# jmb575.net
KiCad netlist of a schematic drawn in Altium Designer
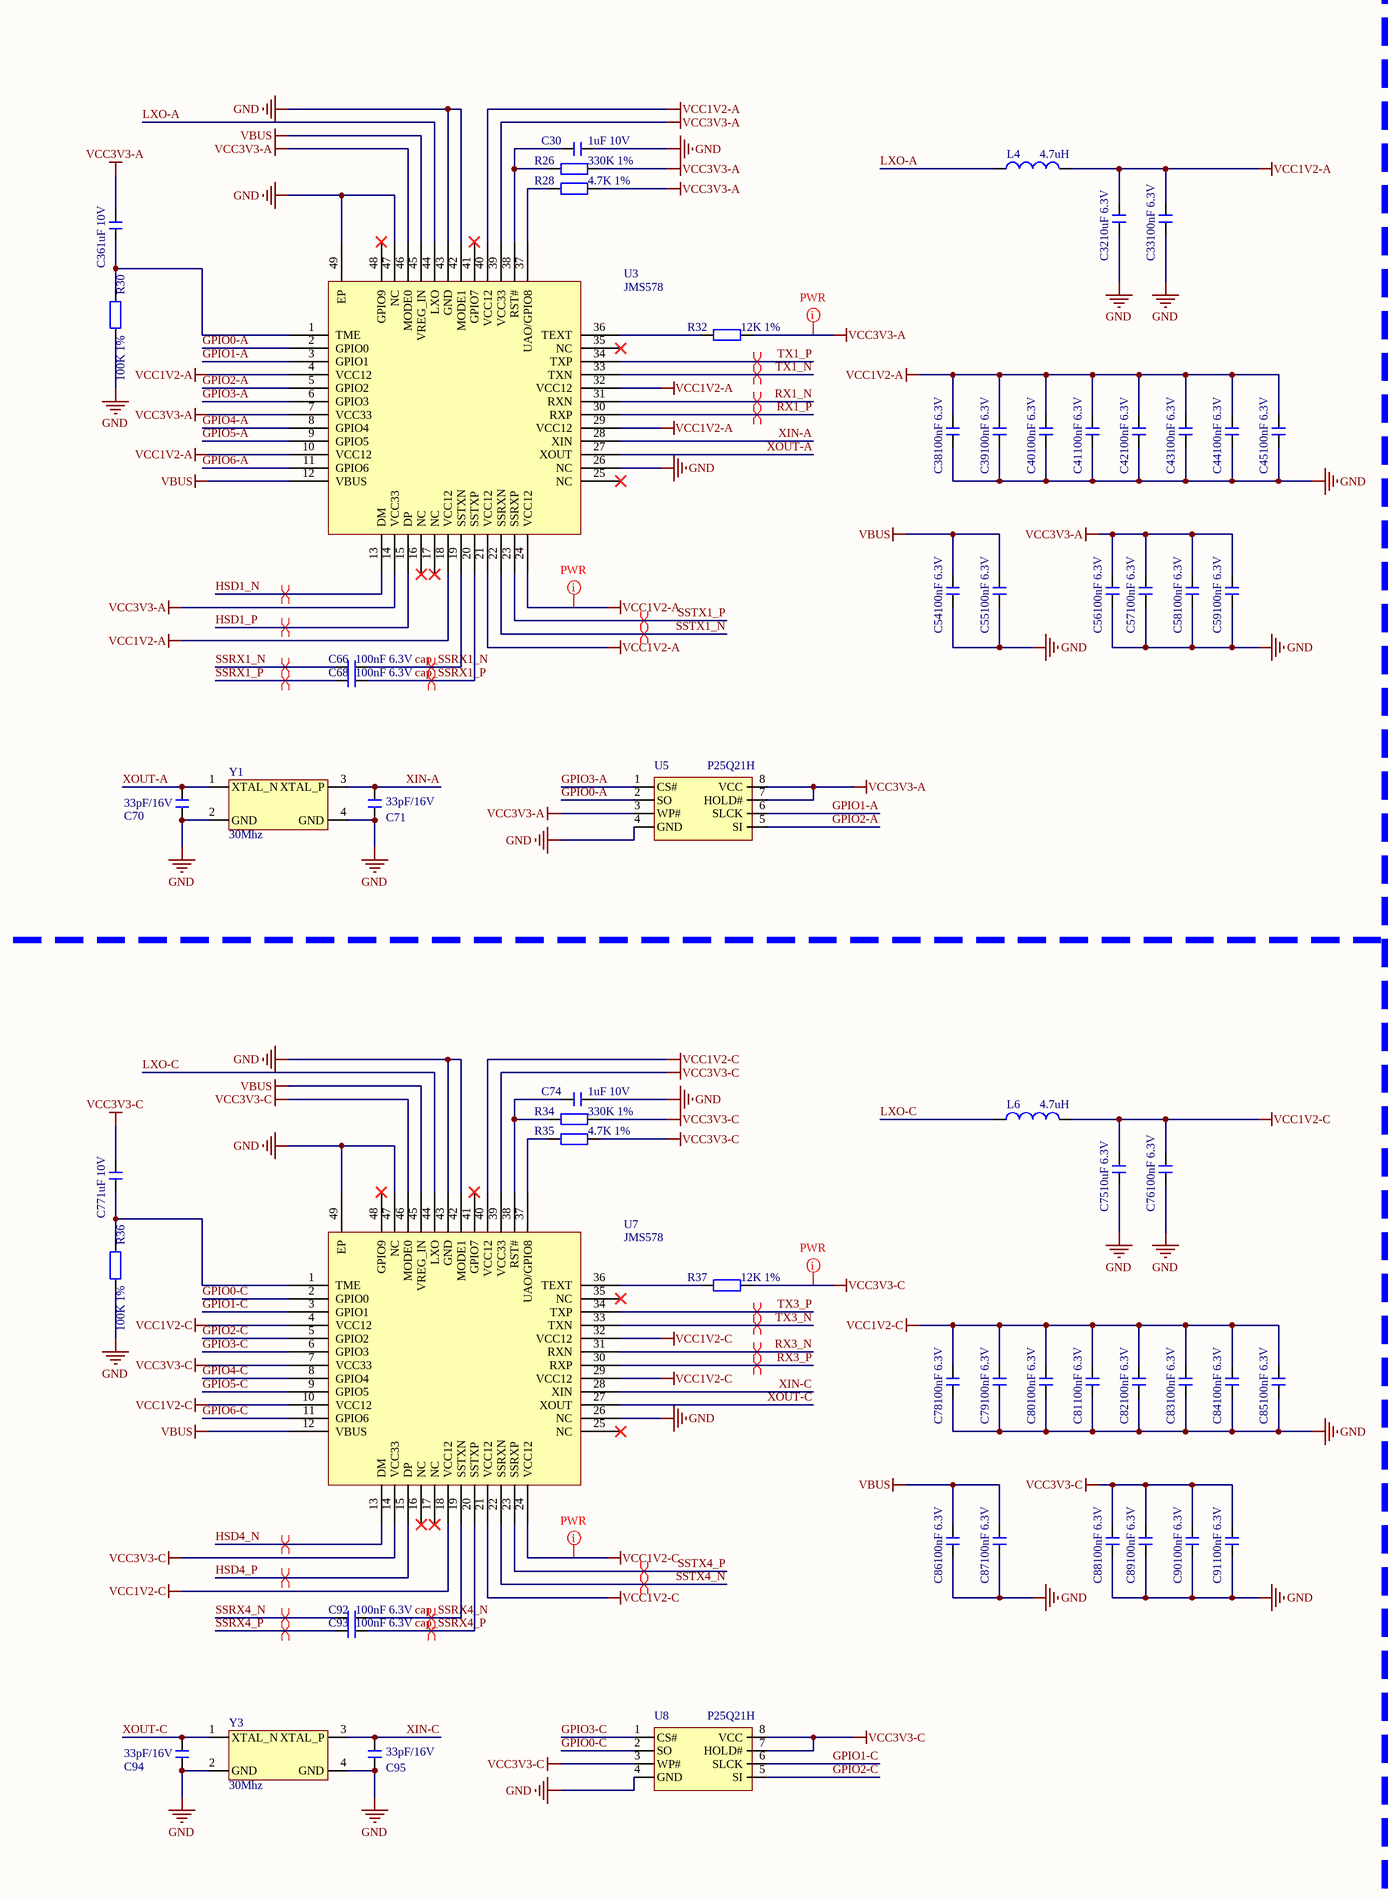
[diagram p0: jmb575.SchDoc, left]
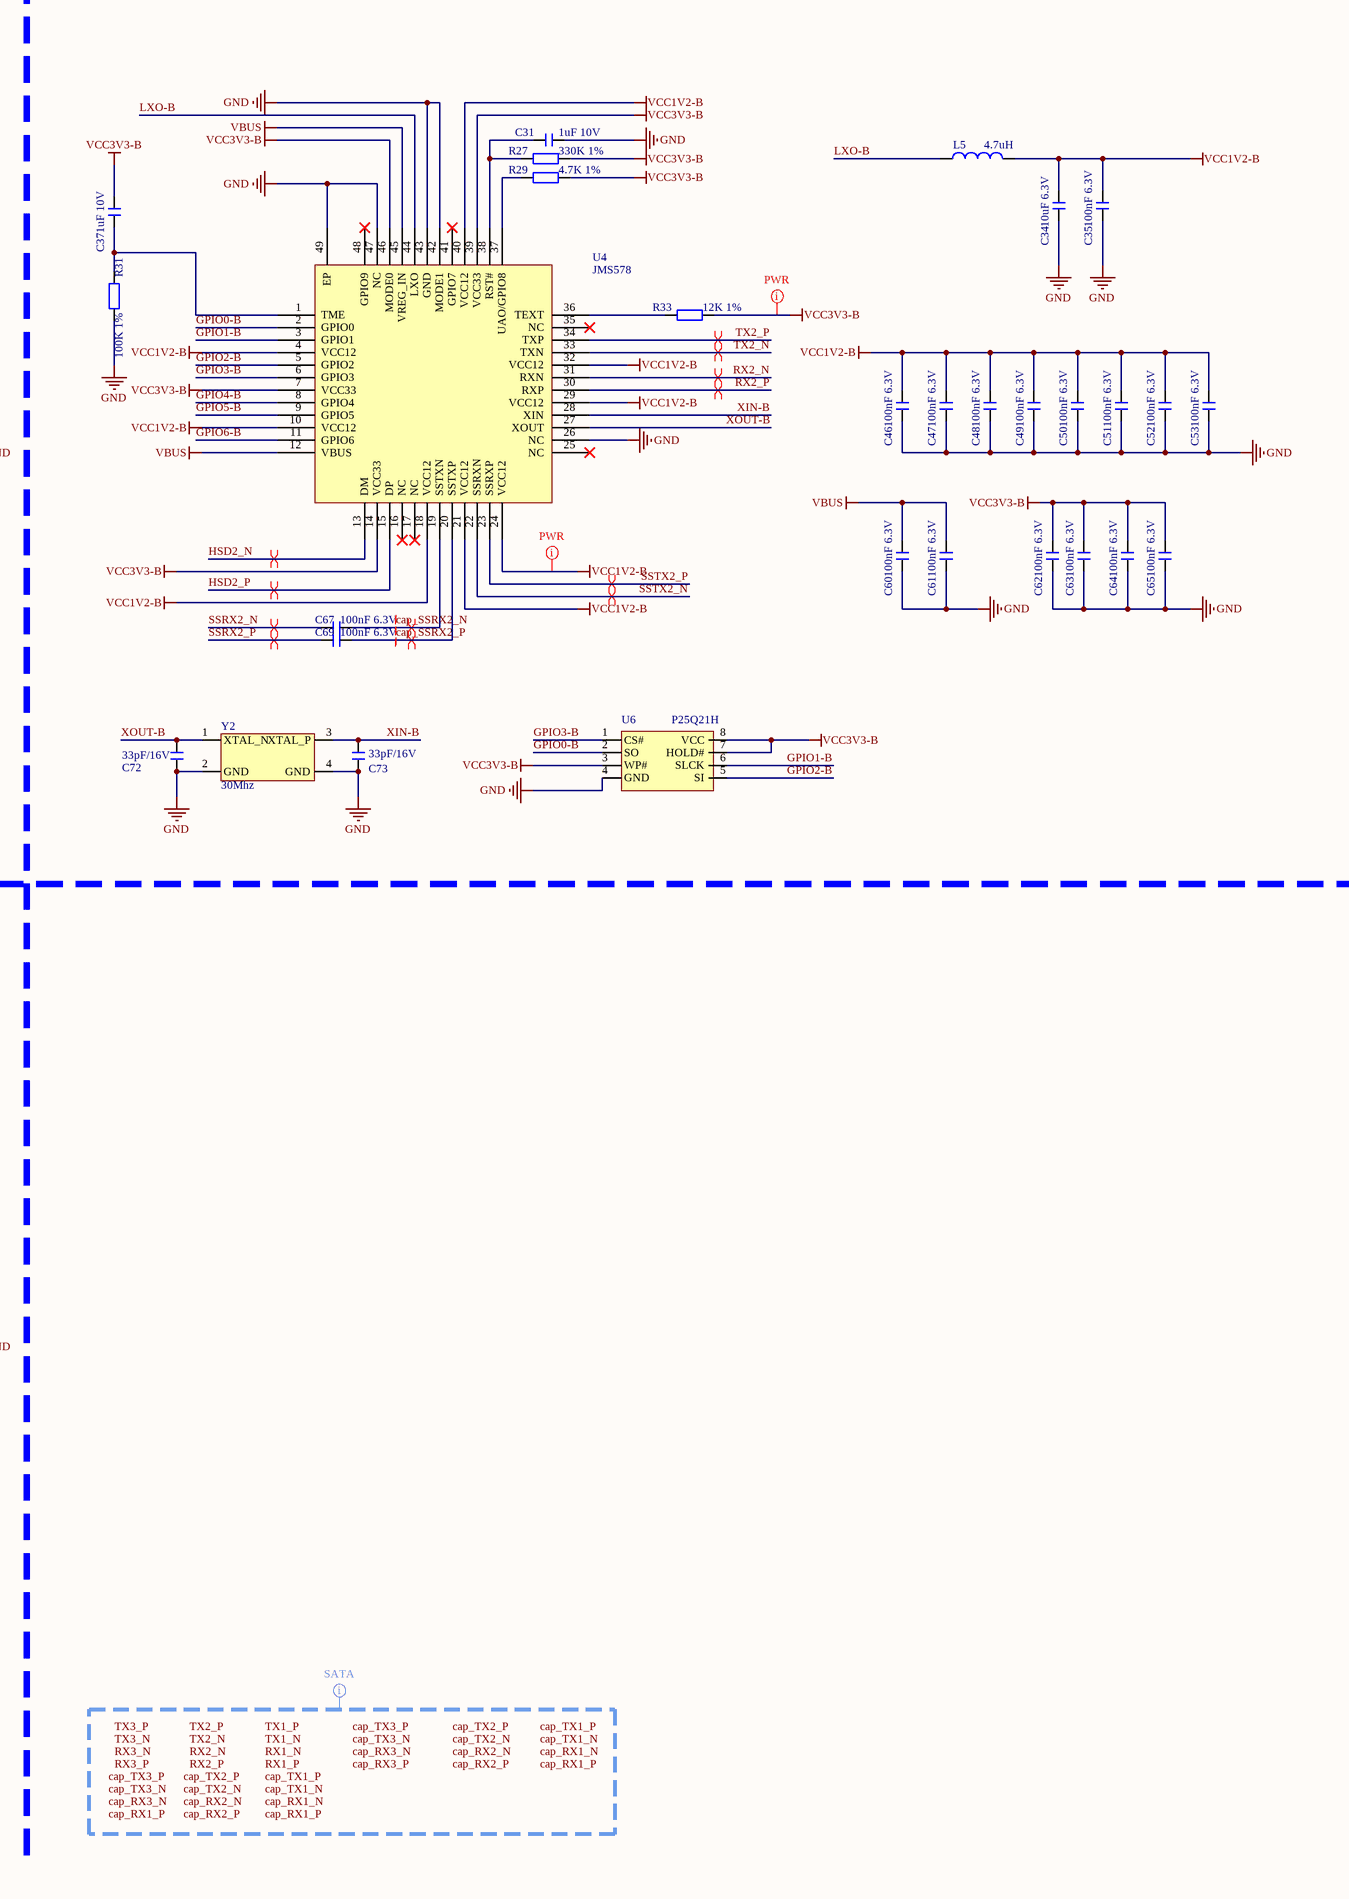
[diagram p1: jmb575.SchDoc, right]

(export (version "E")
  (design (tool "Eeschema 10.0.6"))
  (components
    (comp (ref "C30")
      (value "1uF 10V")
      (footprint "C0402_L")
      (description "无极性贴片电容")
      (fields (field (name "版权归属") "源创客"))
      (libsource (lib "Capacitor") (part "C"))
    )
    (comp (ref "C31")
      (value "1uF 10V")
      (footprint "C0402_L")
      (description "无极性贴片电容")
      (fields (field (name "版权归属") "源创客"))
      (libsource (lib "Capacitor") (part "C"))
    )
    (comp (ref "C32")
      (value "10uF 6.3V")
      (footprint "C0603_L")
      (description "无极性贴片电容")
      (fields (field (name "版权归属") "源创客"))
      (libsource (lib "Capacitor") (part "C"))
    )
    (comp (ref "C33")
      (value "100nF 6.3V")
      (footprint "C0402_L")
      (description "无极性贴片电容")
      (fields (field (name "版权归属") "源创客"))
      (libsource (lib "Capacitor") (part "C"))
    )
    (comp (ref "C34")
      (value "10uF 6.3V")
      (footprint "C0603_L")
      (description "无极性贴片电容")
      (fields (field (name "版权归属") "源创客"))
      (libsource (lib "Capacitor") (part "C"))
    )
    (comp (ref "C35")
      (value "100nF 6.3V")
      (footprint "C0402_L")
      (description "无极性贴片电容")
      (fields (field (name "版权归属") "源创客"))
      (libsource (lib "Capacitor") (part "C"))
    )
    (comp (ref "C36")
      (value "1uF 10V")
      (footprint "C0402_L")
      (description "无极性贴片电容")
      (fields (field (name "版权归属") "源创客"))
      (libsource (lib "Capacitor") (part "C"))
    )
    (comp (ref "C37")
      (value "1uF 10V")
      (footprint "C0402_L")
      (description "无极性贴片电容")
      (fields (field (name "版权归属") "源创客"))
      (libsource (lib "Capacitor") (part "C"))
    )
    (comp (ref "C38")
      (value "100nF 6.3V")
      (footprint "C0402_L")
      (description "无极性贴片电容")
      (fields (field (name "版权归属") "源创客"))
      (libsource (lib "Capacitor") (part "C"))
    )
    (comp (ref "C39")
      (value "100nF 6.3V")
      (footprint "C0402_L")
      (description "无极性贴片电容")
      (fields (field (name "版权归属") "源创客"))
      (libsource (lib "Capacitor") (part "C"))
    )
    (comp (ref "C40")
      (value "100nF 6.3V")
      (footprint "C0402_L")
      (description "无极性贴片电容")
      (fields (field (name "版权归属") "源创客"))
      (libsource (lib "Capacitor") (part "C"))
    )
    (comp (ref "C41")
      (value "100nF 6.3V")
      (footprint "C0402_L")
      (description "无极性贴片电容")
      (fields (field (name "版权归属") "源创客"))
      (libsource (lib "Capacitor") (part "C"))
    )
    (comp (ref "C42")
      (value "100nF 6.3V")
      (footprint "C0402_L")
      (description "无极性贴片电容")
      (fields (field (name "版权归属") "源创客"))
      (libsource (lib "Capacitor") (part "C"))
    )
    (comp (ref "C43")
      (value "100nF 6.3V")
      (footprint "C0402_L")
      (description "无极性贴片电容")
      (fields (field (name "版权归属") "源创客"))
      (libsource (lib "Capacitor") (part "C"))
    )
    (comp (ref "C44")
      (value "100nF 6.3V")
      (footprint "C0402_L")
      (description "无极性贴片电容")
      (fields (field (name "版权归属") "源创客"))
      (libsource (lib "Capacitor") (part "C"))
    )
    (comp (ref "C45")
      (value "100nF 6.3V")
      (footprint "C0402_L")
      (description "无极性贴片电容")
      (fields (field (name "版权归属") "源创客"))
      (libsource (lib "Capacitor") (part "C"))
    )
    (comp (ref "C46")
      (value "100nF 6.3V")
      (footprint "C0402_L")
      (description "无极性贴片电容")
      (fields (field (name "版权归属") "源创客"))
      (libsource (lib "Capacitor") (part "C"))
    )
    (comp (ref "C47")
      (value "100nF 6.3V")
      (footprint "C0402_L")
      (description "无极性贴片电容")
      (fields (field (name "版权归属") "源创客"))
      (libsource (lib "Capacitor") (part "C"))
    )
    (comp (ref "C48")
      (value "100nF 6.3V")
      (footprint "C0402_L")
      (description "无极性贴片电容")
      (fields (field (name "版权归属") "源创客"))
      (libsource (lib "Capacitor") (part "C"))
    )
    (comp (ref "C49")
      (value "100nF 6.3V")
      (footprint "C0402_L")
      (description "无极性贴片电容")
      (fields (field (name "版权归属") "源创客"))
      (libsource (lib "Capacitor") (part "C"))
    )
    (comp (ref "C50")
      (value "100nF 6.3V")
      (footprint "C0402_L")
      (description "无极性贴片电容")
      (fields (field (name "版权归属") "源创客"))
      (libsource (lib "Capacitor") (part "C"))
    )
    (comp (ref "C51")
      (value "100nF 6.3V")
      (footprint "C0402_L")
      (description "无极性贴片电容")
      (fields (field (name "版权归属") "源创客"))
      (libsource (lib "Capacitor") (part "C"))
    )
    (comp (ref "C52")
      (value "100nF 6.3V")
      (footprint "C0402_L")
      (description "无极性贴片电容")
      (fields (field (name "版权归属") "源创客"))
      (libsource (lib "Capacitor") (part "C"))
    )
    (comp (ref "C53")
      (value "100nF 6.3V")
      (footprint "C0402_L")
      (description "无极性贴片电容")
      (fields (field (name "版权归属") "源创客"))
      (libsource (lib "Capacitor") (part "C"))
    )
    (comp (ref "C54")
      (value "100nF 6.3V")
      (footprint "C0402_L")
      (description "无极性贴片电容")
      (fields (field (name "版权归属") "源创客"))
      (libsource (lib "Capacitor") (part "C"))
    )
    (comp (ref "C55")
      (value "100nF 6.3V")
      (footprint "C0402_L")
      (description "无极性贴片电容")
      (fields (field (name "版权归属") "源创客"))
      (libsource (lib "Capacitor") (part "C"))
    )
    (comp (ref "C56")
      (value "100nF 6.3V")
      (footprint "C0402_L")
      (description "无极性贴片电容")
      (fields (field (name "版权归属") "源创客"))
      (libsource (lib "Capacitor") (part "C"))
    )
    (comp (ref "C57")
      (value "100nF 6.3V")
      (footprint "C0402_L")
      (description "无极性贴片电容")
      (fields (field (name "版权归属") "源创客"))
      (libsource (lib "Capacitor") (part "C"))
    )
    (comp (ref "C58")
      (value "100nF 6.3V")
      (footprint "C0402_L")
      (description "无极性贴片电容")
      (fields (field (name "版权归属") "源创客"))
      (libsource (lib "Capacitor") (part "C"))
    )
    (comp (ref "C59")
      (value "100nF 6.3V")
      (footprint "C0402_L")
      (description "无极性贴片电容")
      (fields (field (name "版权归属") "源创客"))
      (libsource (lib "Capacitor") (part "C"))
    )
    (comp (ref "C60")
      (value "100nF 6.3V")
      (footprint "C0402_L")
      (description "无极性贴片电容")
      (fields (field (name "版权归属") "源创客"))
      (libsource (lib "Capacitor") (part "C"))
    )
    (comp (ref "C61")
      (value "100nF 6.3V")
      (footprint "C0402_L")
      (description "无极性贴片电容")
      (fields (field (name "版权归属") "源创客"))
      (libsource (lib "Capacitor") (part "C"))
    )
    (comp (ref "C62")
      (value "100nF 6.3V")
      (footprint "C0402_L")
      (description "无极性贴片电容")
      (fields (field (name "版权归属") "源创客"))
      (libsource (lib "Capacitor") (part "C"))
    )
    (comp (ref "C63")
      (value "100nF 6.3V")
      (footprint "C0402_L")
      (description "无极性贴片电容")
      (fields (field (name "版权归属") "源创客"))
      (libsource (lib "Capacitor") (part "C"))
    )
    (comp (ref "C64")
      (value "100nF 6.3V")
      (footprint "C0402_L")
      (description "无极性贴片电容")
      (fields (field (name "版权归属") "源创客"))
      (libsource (lib "Capacitor") (part "C"))
    )
    (comp (ref "C65")
      (value "100nF 6.3V")
      (footprint "C0402_L")
      (description "无极性贴片电容")
      (fields (field (name "版权归属") "源创客"))
      (libsource (lib "Capacitor") (part "C"))
    )
    (comp (ref "C66")
      (value "100nF 6.3V")
      (footprint "C0402_L")
      (description "无极性贴片电容")
      (fields (field (name "版权归属") "源创客"))
      (libsource (lib "Capacitor") (part "C"))
    )
    (comp (ref "C67")
      (value "100nF 6.3V")
      (footprint "C0402_L")
      (description "无极性贴片电容")
      (fields (field (name "版权归属") "源创客"))
      (libsource (lib "Capacitor") (part "C"))
    )
    (comp (ref "C68")
      (value "100nF 6.3V")
      (footprint "C0402_L")
      (description "无极性贴片电容")
      (fields (field (name "版权归属") "源创客"))
      (libsource (lib "Capacitor") (part "C"))
    )
    (comp (ref "C69")
      (value "100nF 6.3V")
      (footprint "C0402_L")
      (description "无极性贴片电容")
      (fields (field (name "版权归属") "源创客"))
      (libsource (lib "Capacitor") (part "C"))
    )
    (comp (ref "C70")
      (value "33pF/16V")
      (footprint "C0402_L")
      (description "无极性贴片电容")
      (fields (field (name "版权归属") "源创客"))
      (libsource (lib "Capacitor") (part "C"))
    )
    (comp (ref "C71")
      (value "33pF/16V")
      (footprint "C0402_L")
      (description "无极性贴片电容")
      (fields (field (name "版权归属") "源创客"))
      (libsource (lib "Capacitor") (part "C"))
    )
    (comp (ref "C72")
      (value "33pF/16V")
      (footprint "C0402_L")
      (description "无极性贴片电容")
      (fields (field (name "版权归属") "源创客"))
      (libsource (lib "Capacitor") (part "C"))
    )
    (comp (ref "C73")
      (value "33pF/16V")
      (footprint "C0402_L")
      (description "无极性贴片电容")
      (fields (field (name "版权归属") "源创客"))
      (libsource (lib "Capacitor") (part "C"))
    )
    (comp (ref "C74")
      (value "1uF 10V")
      (footprint "C0402_L")
      (description "无极性贴片电容")
      (fields (field (name "版权归属") "源创客"))
      (libsource (lib "Capacitor") (part "C"))
    )
    (comp (ref "C75")
      (value "10uF 6.3V")
      (footprint "C0603_L")
      (description "无极性贴片电容")
      (fields (field (name "版权归属") "源创客"))
      (libsource (lib "Capacitor") (part "C"))
    )
    (comp (ref "C76")
      (value "100nF 6.3V")
      (footprint "C0402_L")
      (description "无极性贴片电容")
      (fields (field (name "版权归属") "源创客"))
      (libsource (lib "Capacitor") (part "C"))
    )
    (comp (ref "C77")
      (value "1uF 10V")
      (footprint "C0402_L")
      (description "无极性贴片电容")
      (fields (field (name "版权归属") "源创客"))
      (libsource (lib "Capacitor") (part "C"))
    )
    (comp (ref "C78")
      (value "100nF 6.3V")
      (footprint "C0402_L")
      (description "无极性贴片电容")
      (fields (field (name "版权归属") "源创客"))
      (libsource (lib "Capacitor") (part "C"))
    )
    (comp (ref "C79")
      (value "100nF 6.3V")
      (footprint "C0402_L")
      (description "无极性贴片电容")
      (fields (field (name "版权归属") "源创客"))
      (libsource (lib "Capacitor") (part "C"))
    )
    (comp (ref "C80")
      (value "100nF 6.3V")
      (footprint "C0402_L")
      (description "无极性贴片电容")
      (fields (field (name "版权归属") "源创客"))
      (libsource (lib "Capacitor") (part "C"))
    )
    (comp (ref "C81")
      (value "100nF 6.3V")
      (footprint "C0402_L")
      (description "无极性贴片电容")
      (fields (field (name "版权归属") "源创客"))
      (libsource (lib "Capacitor") (part "C"))
    )
    (comp (ref "C82")
      (value "100nF 6.3V")
      (footprint "C0402_L")
      (description "无极性贴片电容")
      (fields (field (name "版权归属") "源创客"))
      (libsource (lib "Capacitor") (part "C"))
    )
    (comp (ref "C83")
      (value "100nF 6.3V")
      (footprint "C0402_L")
      (description "无极性贴片电容")
      (fields (field (name "版权归属") "源创客"))
      (libsource (lib "Capacitor") (part "C"))
    )
    (comp (ref "C84")
      (value "100nF 6.3V")
      (footprint "C0402_L")
      (description "无极性贴片电容")
      (fields (field (name "版权归属") "源创客"))
      (libsource (lib "Capacitor") (part "C"))
    )
    (comp (ref "C85")
      (value "100nF 6.3V")
      (footprint "C0402_L")
      (description "无极性贴片电容")
      (fields (field (name "版权归属") "源创客"))
      (libsource (lib "Capacitor") (part "C"))
    )
    (comp (ref "C86")
      (value "100nF 6.3V")
      (footprint "C0402_L")
      (description "无极性贴片电容")
      (fields (field (name "版权归属") "源创客"))
      (libsource (lib "Capacitor") (part "C"))
    )
    (comp (ref "C87")
      (value "100nF 6.3V")
      (footprint "C0402_L")
      (description "无极性贴片电容")
      (fields (field (name "版权归属") "源创客"))
      (libsource (lib "Capacitor") (part "C"))
    )
    (comp (ref "C88")
      (value "100nF 6.3V")
      (footprint "C0402_L")
      (description "无极性贴片电容")
      (fields (field (name "版权归属") "源创客"))
      (libsource (lib "Capacitor") (part "C"))
    )
    (comp (ref "C89")
      (value "100nF 6.3V")
      (footprint "C0402_L")
      (description "无极性贴片电容")
      (fields (field (name "版权归属") "源创客"))
      (libsource (lib "Capacitor") (part "C"))
    )
    (comp (ref "C90")
      (value "100nF 6.3V")
      (footprint "C0402_L")
      (description "无极性贴片电容")
      (fields (field (name "版权归属") "源创客"))
      (libsource (lib "Capacitor") (part "C"))
    )
    (comp (ref "C91")
      (value "100nF 6.3V")
      (footprint "C0402_L")
      (description "无极性贴片电容")
      (fields (field (name "版权归属") "源创客"))
      (libsource (lib "Capacitor") (part "C"))
    )
    (comp (ref "C92")
      (value "100nF 6.3V")
      (footprint "C0402_L")
      (description "无极性贴片电容")
      (fields (field (name "版权归属") "源创客"))
      (libsource (lib "Capacitor") (part "C"))
    )
    (comp (ref "C93")
      (value "100nF 6.3V")
      (footprint "C0402_L")
      (description "无极性贴片电容")
      (fields (field (name "版权归属") "源创客"))
      (libsource (lib "Capacitor") (part "C"))
    )
    (comp (ref "C94")
      (value "33pF/16V")
      (footprint "C0402_L")
      (description "无极性贴片电容")
      (fields (field (name "版权归属") "源创客"))
      (libsource (lib "Capacitor") (part "C"))
    )
    (comp (ref "C95")
      (value "33pF/16V")
      (footprint "C0402_L")
      (description "无极性贴片电容")
      (fields (field (name "版权归属") "源创客"))
      (libsource (lib "Capacitor") (part "C"))
    )
    (comp (ref "L4")
      (value "4.7uH")
      (footprint "NR2520")
      (description "小功率贴片电感")
      (fields (field (name "版权归属") "源创客"))
      (libsource (lib "Inductor") (part "L"))
    )
    (comp (ref "L5")
      (value "4.7uH")
      (footprint "NR2520")
      (description "小功率贴片电感")
      (fields (field (name "版权归属") "源创客"))
      (libsource (lib "Inductor") (part "L"))
    )
    (comp (ref "L6")
      (value "4.7uH")
      (footprint "NR2520")
      (description "小功率贴片电感")
      (fields (field (name "版权归属") "源创客"))
      (libsource (lib "Inductor") (part "L"))
    )
    (comp (ref "R26")
      (value "330K 1%")
      (footprint "R0402_L")
      (description "贴片电阻")
      (fields (field (name "版权归属") "源创客"))
      (libsource (lib "Resistor") (part "R"))
    )
    (comp (ref "R27")
      (value "330K 1%")
      (footprint "R0402_L")
      (description "贴片电阻")
      (fields (field (name "版权归属") "源创客"))
      (libsource (lib "Resistor") (part "R"))
    )
    (comp (ref "R28")
      (value "4.7K 1%")
      (footprint "R0402_L")
      (description "贴片电阻")
      (fields (field (name "版权归属") "源创客"))
      (libsource (lib "Resistor") (part "R"))
    )
    (comp (ref "R29")
      (value "4.7K 1%")
      (footprint "R0402_L")
      (description "贴片电阻")
      (fields (field (name "版权归属") "源创客"))
      (libsource (lib "Resistor") (part "R"))
    )
    (comp (ref "R30")
      (value "100K 1%")
      (footprint "R0402_L")
      (description "贴片电阻")
      (fields (field (name "版权归属") "源创客"))
      (libsource (lib "Resistor") (part "R"))
    )
    (comp (ref "R31")
      (value "100K 1%")
      (footprint "R0402_L")
      (description "贴片电阻")
      (fields (field (name "版权归属") "源创客"))
      (libsource (lib "Resistor") (part "R"))
    )
    (comp (ref "R32")
      (value "12K 1%")
      (footprint "R0402_L")
      (description "贴片电阻")
      (fields (field (name "版权归属") "源创客"))
      (libsource (lib "Resistor") (part "R"))
    )
    (comp (ref "R33")
      (value "12K 1%")
      (footprint "R0402_L")
      (description "贴片电阻")
      (fields (field (name "版权归属") "源创客"))
      (libsource (lib "Resistor") (part "R"))
    )
    (comp (ref "R34")
      (value "330K 1%")
      (footprint "R0402_L")
      (description "贴片电阻")
      (fields (field (name "版权归属") "源创客"))
      (libsource (lib "Resistor") (part "R"))
    )
    (comp (ref "R35")
      (value "4.7K 1%")
      (footprint "R0402_L")
      (description "贴片电阻")
      (fields (field (name "版权归属") "源创客"))
      (libsource (lib "Resistor") (part "R"))
    )
    (comp (ref "R36")
      (value "100K 1%")
      (footprint "R0402_L")
      (description "贴片电阻")
      (fields (field (name "版权归属") "源创客"))
      (libsource (lib "Resistor") (part "R"))
    )
    (comp (ref "R37")
      (value "12K 1%")
      (footprint "R0402_L")
      (description "贴片电阻")
      (fields (field (name "版权归属") "源创客"))
      (libsource (lib "Resistor") (part "R"))
    )
    (comp (ref "U3")
      (value "JMS578")
      (footprint "QFN48-L6.0-W6.0-P0.4")
      (libsource (lib "Brage") (part "JMS578"))
    )
    (comp (ref "U4")
      (value "JMS578")
      (footprint "QFN48-L6.0-W6.0-P0.4")
      (libsource (lib "Brage") (part "JMS578"))
    )
    (comp (ref "U5") (value "P25Q21H") (footprint "SOP8_L") (libsource (lib "Flash") (part "P25D40H")))
    (comp (ref "U6") (value "P25Q21H") (footprint "SOP8_L") (libsource (lib "Flash") (part "P25D40H")))
    (comp (ref "U7")
      (value "JMS578")
      (footprint "QFN48-L6.0-W6.0-P0.4")
      (libsource (lib "Brage") (part "JMS578"))
    )
    (comp (ref "U8") (value "P25Q21H") (footprint "SOP8_L") (libsource (lib "Flash") (part "P25D40H")))
    (comp (ref "Y1") (value "30Mhz") (footprint "OSC 3225-4P") (libsource (lib "Crystal") (part "Crystal")))
    (comp (ref "Y2") (value "30Mhz") (footprint "OSC 3225-4P") (libsource (lib "Crystal") (part "Crystal")))
    (comp (ref "Y3") (value "30Mhz") (footprint "OSC 3225-4P") (libsource (lib "Crystal") (part "Crystal")))
  )
  (nets
    (net (code "1") (name "/GPIO0-A") (class "Default")
      (node (ref "U3") (pin "2") (pinfunction "GPIO0_2") (pintype "passive"))
      (node (ref "U5") (pin "2") (pinfunction "SO_2") (pintype "passive"))
    )
    (net (code "2") (name "/GPIO0-B") (class "Default")
      (node (ref "U4") (pin "2") (pinfunction "GPIO0_2") (pintype "passive"))
      (node (ref "U6") (pin "2") (pinfunction "SO_2") (pintype "passive"))
    )
    (net (code "3") (name "/GPIO0-C") (class "Default")
      (node (ref "U7") (pin "2") (pinfunction "GPIO0_2") (pintype "passive"))
      (node (ref "U8") (pin "2") (pinfunction "SO_2") (pintype "passive"))
    )
    (net (code "4") (name "/GPIO1-A") (class "Default")
      (node (ref "U3") (pin "3") (pinfunction "GPIO1_3") (pintype "passive"))
      (node (ref "U5") (pin "6") (pinfunction "SLCK_6") (pintype "passive"))
    )
    (net (code "5") (name "/GPIO1-B") (class "Default")
      (node (ref "U4") (pin "3") (pinfunction "GPIO1_3") (pintype "passive"))
      (node (ref "U6") (pin "6") (pinfunction "SLCK_6") (pintype "passive"))
    )
    (net (code "6") (name "/GPIO1-C") (class "Default")
      (node (ref "U7") (pin "3") (pinfunction "GPIO1_3") (pintype "passive"))
      (node (ref "U8") (pin "6") (pinfunction "SLCK_6") (pintype "passive"))
    )
    (net (code "7") (name "/GPIO2-A") (class "Default")
      (node (ref "U3") (pin "5") (pinfunction "GPIO2_5") (pintype "passive"))
      (node (ref "U5") (pin "5") (pinfunction "SI_5") (pintype "passive"))
    )
    (net (code "8") (name "/GPIO2-B") (class "Default")
      (node (ref "U4") (pin "5") (pinfunction "GPIO2_5") (pintype "passive"))
      (node (ref "U6") (pin "5") (pinfunction "SI_5") (pintype "passive"))
    )
    (net (code "9") (name "/GPIO2-C") (class "Default")
      (node (ref "U7") (pin "5") (pinfunction "GPIO2_5") (pintype "passive"))
      (node (ref "U8") (pin "5") (pinfunction "SI_5") (pintype "passive"))
    )
    (net (code "10") (name "/GPIO3-A") (class "Default")
      (node (ref "U3") (pin "6") (pinfunction "GPIO3_6") (pintype "passive"))
      (node (ref "U5") (pin "1") (pinfunction "CS#_1") (pintype "passive"))
    )
    (net (code "11") (name "/GPIO3-B") (class "Default")
      (node (ref "U4") (pin "6") (pinfunction "GPIO3_6") (pintype "passive"))
      (node (ref "U6") (pin "1") (pinfunction "CS#_1") (pintype "passive"))
    )
    (net (code "12") (name "/GPIO3-C") (class "Default")
      (node (ref "U7") (pin "6") (pinfunction "GPIO3_6") (pintype "passive"))
      (node (ref "U8") (pin "1") (pinfunction "CS#_1") (pintype "passive"))
    )
    (net (code "13") (name "/GPIO4-A") (class "Default")
      (node (ref "U3") (pin "8") (pinfunction "GPIO4_8") (pintype "passive"))
    )
    (net (code "14") (name "/GPIO4-B") (class "Default")
      (node (ref "U4") (pin "8") (pinfunction "GPIO4_8") (pintype "passive"))
    )
    (net (code "15") (name "/GPIO4-C") (class "Default")
      (node (ref "U7") (pin "8") (pinfunction "GPIO4_8") (pintype "passive"))
    )
    (net (code "16") (name "/GPIO5-A") (class "Default")
      (node (ref "U3") (pin "9") (pinfunction "GPIO5_9") (pintype "passive"))
    )
    (net (code "17") (name "/GPIO5-B") (class "Default")
      (node (ref "U4") (pin "9") (pinfunction "GPIO5_9") (pintype "passive"))
    )
    (net (code "18") (name "/GPIO5-C") (class "Default")
      (node (ref "U7") (pin "9") (pinfunction "GPIO5_9") (pintype "passive"))
    )
    (net (code "19") (name "/GPIO6-A") (class "Default")
      (node (ref "U3") (pin "11") (pinfunction "GPIO6_11") (pintype "passive"))
    )
    (net (code "20") (name "/GPIO6-B") (class "Default")
      (node (ref "U4") (pin "11") (pinfunction "GPIO6_11") (pintype "passive"))
    )
    (net (code "21") (name "/GPIO6-C") (class "Default")
      (node (ref "U7") (pin "11") (pinfunction "GPIO6_11") (pintype "passive"))
    )
    (net (code "22") (name "/HSD1_N") (class "Default")
      (node (ref "U3") (pin "13") (pinfunction "DM_13") (pintype "passive"))
    )
    (net (code "23") (name "/HSD1_P") (class "Default")
      (node (ref "U3") (pin "15") (pinfunction "DP_15") (pintype "passive"))
    )
    (net (code "24") (name "/HSD2_N") (class "Default")
      (node (ref "U4") (pin "13") (pinfunction "DM_13") (pintype "passive"))
    )
    (net (code "25") (name "/HSD2_P") (class "Default")
      (node (ref "U4") (pin "15") (pinfunction "DP_15") (pintype "passive"))
    )
    (net (code "26") (name "/HSD4_N") (class "Default")
      (node (ref "U7") (pin "13") (pinfunction "DM_13") (pintype "passive"))
    )
    (net (code "27") (name "/HSD4_P") (class "Default")
      (node (ref "U7") (pin "15") (pinfunction "DP_15") (pintype "passive"))
    )
    (net (code "28") (name "/LXO-A") (class "Default")
      (node (ref "L4") (pin "1") (pinfunction "1_1") (pintype "passive"))
      (node (ref "U3") (pin "44") (pinfunction "LXO_44") (pintype "passive"))
    )
    (net (code "29") (name "/LXO-B") (class "Default")
      (node (ref "L5") (pin "1") (pinfunction "1_1") (pintype "passive"))
      (node (ref "U4") (pin "44") (pinfunction "LXO_44") (pintype "passive"))
    )
    (net (code "30") (name "/LXO-C") (class "Default")
      (node (ref "L6") (pin "1") (pinfunction "1_1") (pintype "passive"))
      (node (ref "U7") (pin "44") (pinfunction "LXO_44") (pintype "passive"))
    )
    (net (code "31") (name "/RX1_N") (class "Default")
      (node (ref "U3") (pin "31") (pinfunction "RXN_31") (pintype "passive"))
    )
    (net (code "32") (name "/RX1_P") (class "Default")
      (node (ref "U3") (pin "30") (pinfunction "RXP_30") (pintype "passive"))
    )
    (net (code "33") (name "/RX2_N") (class "Default")
      (node (ref "U4") (pin "31") (pinfunction "RXN_31") (pintype "passive"))
    )
    (net (code "34") (name "/RX2_P") (class "Default")
      (node (ref "U4") (pin "30") (pinfunction "RXP_30") (pintype "passive"))
    )
    (net (code "35") (name "/RX3_N") (class "Default")
      (node (ref "U7") (pin "31") (pinfunction "RXN_31") (pintype "passive"))
    )
    (net (code "36") (name "/RX3_P") (class "Default")
      (node (ref "U7") (pin "30") (pinfunction "RXP_30") (pintype "passive"))
    )
    (net (code "37") (name "/SSRX1_N") (class "Default")
      (node (ref "C66") (pin "1") (pinfunction "1_1") (pintype "passive"))
    )
    (net (code "38") (name "/SSRX1_P") (class "Default")
      (node (ref "C68") (pin "1") (pinfunction "1_1") (pintype "passive"))
    )
    (net (code "39") (name "/SSRX2_N") (class "Default")
      (node (ref "C67") (pin "1") (pinfunction "1_1") (pintype "passive"))
    )
    (net (code "40") (name "/SSRX2_P") (class "Default")
      (node (ref "C69") (pin "1") (pinfunction "1_1") (pintype "passive"))
    )
    (net (code "41") (name "/SSRX4_N") (class "Default")
      (node (ref "C92") (pin "1") (pinfunction "1_1") (pintype "passive"))
    )
    (net (code "42") (name "/SSRX4_P") (class "Default")
      (node (ref "C93") (pin "1") (pinfunction "1_1") (pintype "passive"))
    )
    (net (code "43") (name "/SSTX1_N") (class "Default")
      (node (ref "U3") (pin "22") (pinfunction "SSRXN_22") (pintype "passive"))
    )
    (net (code "44") (name "/SSTX1_P") (class "Default")
      (node (ref "U3") (pin "23") (pinfunction "SSRXP_23") (pintype "passive"))
    )
    (net (code "45") (name "/SSTX2_N") (class "Default")
      (node (ref "U4") (pin "22") (pinfunction "SSRXN_22") (pintype "passive"))
    )
    (net (code "46") (name "/SSTX2_P") (class "Default")
      (node (ref "U4") (pin "23") (pinfunction "SSRXP_23") (pintype "passive"))
    )
    (net (code "47") (name "/SSTX4_N") (class "Default")
      (node (ref "U7") (pin "22") (pinfunction "SSRXN_22") (pintype "passive"))
    )
    (net (code "48") (name "/SSTX4_P") (class "Default")
      (node (ref "U7") (pin "23") (pinfunction "SSRXP_23") (pintype "passive"))
    )
    (net (code "49") (name "/TX1_N") (class "Default")
      (node (ref "U3") (pin "33") (pinfunction "TXN_33") (pintype "passive"))
    )
    (net (code "50") (name "/TX1_P") (class "Default")
      (node (ref "U3") (pin "34") (pinfunction "TXP_34") (pintype "passive"))
    )
    (net (code "51") (name "/TX2_N") (class "Default")
      (node (ref "U4") (pin "33") (pinfunction "TXN_33") (pintype "passive"))
    )
    (net (code "52") (name "/TX2_P") (class "Default")
      (node (ref "U4") (pin "34") (pinfunction "TXP_34") (pintype "passive"))
    )
    (net (code "53") (name "/TX3_N") (class "Default")
      (node (ref "U7") (pin "33") (pinfunction "TXN_33") (pintype "passive"))
    )
    (net (code "54") (name "/TX3_P") (class "Default")
      (node (ref "U7") (pin "34") (pinfunction "TXP_34") (pintype "passive"))
    )
    (net (code "55") (name "/XIN-A") (class "Default")
      (node (ref "C71") (pin "1") (pinfunction "1_1") (pintype "passive"))
      (node (ref "U3") (pin "28") (pinfunction "XIN_28") (pintype "passive"))
      (node (ref "Y1") (pin "3") (pinfunction "XTAL_P_3") (pintype "passive"))
    )
    (net (code "56") (name "/XIN-B") (class "Default")
      (node (ref "C73") (pin "1") (pinfunction "1_1") (pintype "passive"))
      (node (ref "U4") (pin "28") (pinfunction "XIN_28") (pintype "passive"))
      (node (ref "Y2") (pin "3") (pinfunction "XTAL_P_3") (pintype "passive"))
    )
    (net (code "57") (name "/XIN-C") (class "Default")
      (node (ref "C95") (pin "1") (pinfunction "1_1") (pintype "passive"))
      (node (ref "U7") (pin "28") (pinfunction "XIN_28") (pintype "passive"))
      (node (ref "Y3") (pin "3") (pinfunction "XTAL_P_3") (pintype "passive"))
    )
    (net (code "58") (name "/XOUT-A") (class "Default")
      (node (ref "C70") (pin "1") (pinfunction "1_1") (pintype "passive"))
      (node (ref "U3") (pin "27") (pinfunction "XOUT_27") (pintype "passive"))
      (node (ref "Y1") (pin "1") (pinfunction "XTAL_N_1") (pintype "passive"))
    )
    (net (code "59") (name "/XOUT-B") (class "Default")
      (node (ref "C72") (pin "1") (pinfunction "1_1") (pintype "passive"))
      (node (ref "U4") (pin "27") (pinfunction "XOUT_27") (pintype "passive"))
      (node (ref "Y2") (pin "1") (pinfunction "XTAL_N_1") (pintype "passive"))
    )
    (net (code "60") (name "/XOUT-C") (class "Default")
      (node (ref "C94") (pin "1") (pinfunction "1_1") (pintype "passive"))
      (node (ref "U7") (pin "27") (pinfunction "XOUT_27") (pintype "passive"))
      (node (ref "Y3") (pin "1") (pinfunction "XTAL_N_1") (pintype "passive"))
    )
    (net (code "67") (name "/cap_SSRX1_N") (class "Default")
      (node (ref "C66") (pin "2") (pinfunction "2_2") (pintype "passive"))
      (node (ref "U3") (pin "19") (pinfunction "SSTXN_19") (pintype "passive"))
    )
    (net (code "68") (name "/cap_SSRX1_P") (class "Default")
      (node (ref "C68") (pin "2") (pinfunction "2_2") (pintype "passive"))
      (node (ref "U3") (pin "20") (pinfunction "SSTXP_20") (pintype "passive"))
    )
    (net (code "69") (name "/cap_SSRX2_N") (class "Default")
      (node (ref "C67") (pin "2") (pinfunction "2_2") (pintype "passive"))
      (node (ref "U4") (pin "19") (pinfunction "SSTXN_19") (pintype "passive"))
    )
    (net (code "70") (name "/cap_SSRX2_P") (class "Default")
      (node (ref "C69") (pin "2") (pinfunction "2_2") (pintype "passive"))
      (node (ref "U4") (pin "20") (pinfunction "SSTXP_20") (pintype "passive"))
    )
    (net (code "71") (name "/cap_SSRX4_N") (class "Default")
      (node (ref "C92") (pin "2") (pinfunction "2_2") (pintype "passive"))
      (node (ref "U7") (pin "19") (pinfunction "SSTXN_19") (pintype "passive"))
    )
    (net (code "72") (name "/cap_SSRX4_P") (class "Default")
      (node (ref "C93") (pin "2") (pinfunction "2_2") (pintype "passive"))
      (node (ref "U7") (pin "20") (pinfunction "SSTXP_20") (pintype "passive"))
    )
    (net (code "79") (name "GND") (class "Default")
      (node (ref "C30") (pin "1") (pinfunction "1_1") (pintype "passive"))
      (node (ref "C31") (pin "1") (pinfunction "1_1") (pintype "passive"))
      (node (ref "C32") (pin "1") (pinfunction "1_1") (pintype "passive"))
      (node (ref "C33") (pin "1") (pinfunction "1_1") (pintype "passive"))
      (node (ref "C34") (pin "1") (pinfunction "1_1") (pintype "passive"))
      (node (ref "C35") (pin "1") (pinfunction "1_1") (pintype "passive"))
      (node (ref "C38") (pin "1") (pinfunction "1_1") (pintype "passive"))
      (node (ref "C39") (pin "1") (pinfunction "1_1") (pintype "passive"))
      (node (ref "C40") (pin "1") (pinfunction "1_1") (pintype "passive"))
      (node (ref "C41") (pin "1") (pinfunction "1_1") (pintype "passive"))
      (node (ref "C42") (pin "1") (pinfunction "1_1") (pintype "passive"))
      (node (ref "C43") (pin "1") (pinfunction "1_1") (pintype "passive"))
      (node (ref "C44") (pin "1") (pinfunction "1_1") (pintype "passive"))
      (node (ref "C45") (pin "1") (pinfunction "1_1") (pintype "passive"))
      (node (ref "C46") (pin "1") (pinfunction "1_1") (pintype "passive"))
      (node (ref "C47") (pin "1") (pinfunction "1_1") (pintype "passive"))
      (node (ref "C48") (pin "1") (pinfunction "1_1") (pintype "passive"))
      (node (ref "C49") (pin "1") (pinfunction "1_1") (pintype "passive"))
      (node (ref "C50") (pin "1") (pinfunction "1_1") (pintype "passive"))
      (node (ref "C51") (pin "1") (pinfunction "1_1") (pintype "passive"))
      (node (ref "C52") (pin "1") (pinfunction "1_1") (pintype "passive"))
      (node (ref "C53") (pin "1") (pinfunction "1_1") (pintype "passive"))
      (node (ref "C54") (pin "1") (pinfunction "1_1") (pintype "passive"))
      (node (ref "C55") (pin "1") (pinfunction "1_1") (pintype "passive"))
      (node (ref "C56") (pin "1") (pinfunction "1_1") (pintype "passive"))
      (node (ref "C57") (pin "1") (pinfunction "1_1") (pintype "passive"))
      (node (ref "C58") (pin "1") (pinfunction "1_1") (pintype "passive"))
      (node (ref "C59") (pin "1") (pinfunction "1_1") (pintype "passive"))
      (node (ref "C60") (pin "1") (pinfunction "1_1") (pintype "passive"))
      (node (ref "C61") (pin "1") (pinfunction "1_1") (pintype "passive"))
      (node (ref "C62") (pin "1") (pinfunction "1_1") (pintype "passive"))
      (node (ref "C63") (pin "1") (pinfunction "1_1") (pintype "passive"))
      (node (ref "C64") (pin "1") (pinfunction "1_1") (pintype "passive"))
      (node (ref "C65") (pin "1") (pinfunction "1_1") (pintype "passive"))
      (node (ref "C70") (pin "2") (pinfunction "2_2") (pintype "passive"))
      (node (ref "C71") (pin "2") (pinfunction "2_2") (pintype "passive"))
      (node (ref "C72") (pin "2") (pinfunction "2_2") (pintype "passive"))
      (node (ref "C73") (pin "2") (pinfunction "2_2") (pintype "passive"))
      (node (ref "C74") (pin "1") (pinfunction "1_1") (pintype "passive"))
      (node (ref "C75") (pin "1") (pinfunction "1_1") (pintype "passive"))
      (node (ref "C76") (pin "1") (pinfunction "1_1") (pintype "passive"))
      (node (ref "C78") (pin "1") (pinfunction "1_1") (pintype "passive"))
      (node (ref "C79") (pin "1") (pinfunction "1_1") (pintype "passive"))
      (node (ref "C80") (pin "1") (pinfunction "1_1") (pintype "passive"))
      (node (ref "C81") (pin "1") (pinfunction "1_1") (pintype "passive"))
      (node (ref "C82") (pin "1") (pinfunction "1_1") (pintype "passive"))
      (node (ref "C83") (pin "1") (pinfunction "1_1") (pintype "passive"))
      (node (ref "C84") (pin "1") (pinfunction "1_1") (pintype "passive"))
      (node (ref "C85") (pin "1") (pinfunction "1_1") (pintype "passive"))
      (node (ref "C86") (pin "1") (pinfunction "1_1") (pintype "passive"))
      (node (ref "C87") (pin "1") (pinfunction "1_1") (pintype "passive"))
      (node (ref "C88") (pin "1") (pinfunction "1_1") (pintype "passive"))
      (node (ref "C89") (pin "1") (pinfunction "1_1") (pintype "passive"))
      (node (ref "C90") (pin "1") (pinfunction "1_1") (pintype "passive"))
      (node (ref "C91") (pin "1") (pinfunction "1_1") (pintype "passive"))
      (node (ref "C94") (pin "2") (pinfunction "2_2") (pintype "passive"))
      (node (ref "C95") (pin "2") (pinfunction "2_2") (pintype "passive"))
      (node (ref "R30") (pin "1") (pinfunction "1_1") (pintype "passive"))
      (node (ref "R31") (pin "1") (pinfunction "1_1") (pintype "passive"))
      (node (ref "R36") (pin "1") (pinfunction "1_1") (pintype "passive"))
      (node (ref "U3") (pin "26") (pinfunction "NC_26") (pintype "passive"))
      (node (ref "U3") (pin "42") (pinfunction "MODE1_42") (pintype "passive"))
      (node (ref "U3") (pin "43") (pinfunction "GND_43") (pintype "passive"))
      (node (ref "U3") (pin "47") (pinfunction "NC_47") (pintype "passive"))
      (node (ref "U3") (pin "49") (pinfunction "EP_49") (pintype "passive"))
      (node (ref "U4") (pin "26") (pinfunction "NC_26") (pintype "passive"))
      (node (ref "U4") (pin "42") (pinfunction "MODE1_42") (pintype "passive"))
      (node (ref "U4") (pin "43") (pinfunction "GND_43") (pintype "passive"))
      (node (ref "U4") (pin "47") (pinfunction "NC_47") (pintype "passive"))
      (node (ref "U4") (pin "49") (pinfunction "EP_49") (pintype "passive"))
      (node (ref "U5") (pin "4") (pinfunction "GND_4") (pintype "passive"))
      (node (ref "U6") (pin "4") (pinfunction "GND_4") (pintype "passive"))
      (node (ref "U7") (pin "26") (pinfunction "NC_26") (pintype "passive"))
      (node (ref "U7") (pin "42") (pinfunction "MODE1_42") (pintype "passive"))
      (node (ref "U7") (pin "43") (pinfunction "GND_43") (pintype "passive"))
      (node (ref "U7") (pin "47") (pinfunction "NC_47") (pintype "passive"))
      (node (ref "U7") (pin "49") (pinfunction "EP_49") (pintype "passive"))
      (node (ref "U8") (pin "4") (pinfunction "GND_4") (pintype "passive"))
      (node (ref "Y1") (pin "2") (pinfunction "GND_2") (pintype "passive"))
      (node (ref "Y1") (pin "4") (pinfunction "GND_4") (pintype "passive"))
      (node (ref "Y2") (pin "2") (pinfunction "GND_2") (pintype "passive"))
      (node (ref "Y2") (pin "4") (pinfunction "GND_4") (pintype "passive"))
      (node (ref "Y3") (pin "2") (pinfunction "GND_2") (pintype "passive"))
      (node (ref "Y3") (pin "4") (pinfunction "GND_4") (pintype "passive"))
    )
    (net (code "80") (name "Net-(U3-RST#)") (class "Default")
      (node (ref "C30") (pin "2") (pinfunction "2_2") (pintype "passive"))
      (node (ref "R26") (pin "2") (pinfunction "2_2") (pintype "passive"))
      (node (ref "U3") (pin "38") (pinfunction "RST#_38") (pintype "passive"))
    )
    (net (code "81") (name "Net-(U3-TEXT)") (class "Default")
      (node (ref "R32") (pin "2") (pinfunction "2_2") (pintype "passive"))
      (node (ref "U3") (pin "36") (pinfunction "TEXT_36") (pintype "passive"))
    )
    (net (code "82") (name "Net-(U3-TME)") (class "Default")
      (node (ref "C36") (pin "1") (pinfunction "1_1") (pintype "passive"))
      (node (ref "R30") (pin "2") (pinfunction "2_2") (pintype "passive"))
      (node (ref "U3") (pin "1") (pinfunction "TME_1") (pintype "passive"))
    )
    (net (code "83") (name "Net-(U3-UAO{slash}GPIO8)") (class "Default")
      (node (ref "R28") (pin "2") (pinfunction "2_2") (pintype "passive"))
      (node (ref "U3") (pin "37") (pinfunction "UAO/GPIO8_37") (pintype "passive"))
    )
    (net (code "84") (name "Net-(U4-RST#)") (class "Default")
      (node (ref "C31") (pin "2") (pinfunction "2_2") (pintype "passive"))
      (node (ref "R27") (pin "2") (pinfunction "2_2") (pintype "passive"))
      (node (ref "U4") (pin "38") (pinfunction "RST#_38") (pintype "passive"))
    )
    (net (code "85") (name "Net-(U4-TEXT)") (class "Default")
      (node (ref "R33") (pin "2") (pinfunction "2_2") (pintype "passive"))
      (node (ref "U4") (pin "36") (pinfunction "TEXT_36") (pintype "passive"))
    )
    (net (code "86") (name "Net-(U4-TME)") (class "Default")
      (node (ref "C37") (pin "1") (pinfunction "1_1") (pintype "passive"))
      (node (ref "R31") (pin "2") (pinfunction "2_2") (pintype "passive"))
      (node (ref "U4") (pin "1") (pinfunction "TME_1") (pintype "passive"))
    )
    (net (code "87") (name "Net-(U4-UAO{slash}GPIO8)") (class "Default")
      (node (ref "R29") (pin "2") (pinfunction "2_2") (pintype "passive"))
      (node (ref "U4") (pin "37") (pinfunction "UAO/GPIO8_37") (pintype "passive"))
    )
    (net (code "88") (name "Net-(U7-RST#)") (class "Default")
      (node (ref "C74") (pin "2") (pinfunction "2_2") (pintype "passive"))
      (node (ref "R34") (pin "2") (pinfunction "2_2") (pintype "passive"))
      (node (ref "U7") (pin "38") (pinfunction "RST#_38") (pintype "passive"))
    )
    (net (code "89") (name "Net-(U7-TEXT)") (class "Default")
      (node (ref "R37") (pin "2") (pinfunction "2_2") (pintype "passive"))
      (node (ref "U7") (pin "36") (pinfunction "TEXT_36") (pintype "passive"))
    )
    (net (code "90") (name "Net-(U7-TME)") (class "Default")
      (node (ref "C77") (pin "1") (pinfunction "1_1") (pintype "passive"))
      (node (ref "R36") (pin "2") (pinfunction "2_2") (pintype "passive"))
      (node (ref "U7") (pin "1") (pinfunction "TME_1") (pintype "passive"))
    )
    (net (code "91") (name "Net-(U7-UAO{slash}GPIO8)") (class "Default")
      (node (ref "R35") (pin "2") (pinfunction "2_2") (pintype "passive"))
      (node (ref "U7") (pin "37") (pinfunction "UAO/GPIO8_37") (pintype "passive"))
    )
    (net (code "92") (name "VBUS") (class "Default")
      (node (ref "C54") (pin "2") (pinfunction "2_2") (pintype "passive"))
      (node (ref "C55") (pin "2") (pinfunction "2_2") (pintype "passive"))
      (node (ref "C60") (pin "2") (pinfunction "2_2") (pintype "passive"))
      (node (ref "C61") (pin "2") (pinfunction "2_2") (pintype "passive"))
      (node (ref "C86") (pin "2") (pinfunction "2_2") (pintype "passive"))
      (node (ref "C87") (pin "2") (pinfunction "2_2") (pintype "passive"))
      (node (ref "U3") (pin "12") (pinfunction "VBUS_12") (pintype "passive"))
      (node (ref "U3") (pin "45") (pinfunction "VREG_IN_45") (pintype "passive"))
      (node (ref "U4") (pin "12") (pinfunction "VBUS_12") (pintype "passive"))
      (node (ref "U4") (pin "45") (pinfunction "VREG_IN_45") (pintype "passive"))
      (node (ref "U7") (pin "12") (pinfunction "VBUS_12") (pintype "passive"))
      (node (ref "U7") (pin "45") (pinfunction "VREG_IN_45") (pintype "passive"))
    )
    (net (code "93") (name "VCC1V2-A") (class "Default")
      (node (ref "C32") (pin "2") (pinfunction "2_2") (pintype "passive"))
      (node (ref "C33") (pin "2") (pinfunction "2_2") (pintype "passive"))
      (node (ref "C38") (pin "2") (pinfunction "2_2") (pintype "passive"))
      (node (ref "C39") (pin "2") (pinfunction "2_2") (pintype "passive"))
      (node (ref "C40") (pin "2") (pinfunction "2_2") (pintype "passive"))
      (node (ref "C41") (pin "2") (pinfunction "2_2") (pintype "passive"))
      (node (ref "C42") (pin "2") (pinfunction "2_2") (pintype "passive"))
      (node (ref "C43") (pin "2") (pinfunction "2_2") (pintype "passive"))
      (node (ref "C44") (pin "2") (pinfunction "2_2") (pintype "passive"))
      (node (ref "C45") (pin "2") (pinfunction "2_2") (pintype "passive"))
      (node (ref "L4") (pin "2") (pinfunction "2_2") (pintype "passive"))
      (node (ref "U3") (pin "10") (pinfunction "VCC12_10") (pintype "passive"))
      (node (ref "U3") (pin "18") (pinfunction "VCC12_18") (pintype "passive"))
      (node (ref "U3") (pin "21") (pinfunction "VCC12_21") (pintype "passive"))
      (node (ref "U3") (pin "24") (pinfunction "VCC12_24") (pintype "passive"))
      (node (ref "U3") (pin "29") (pinfunction "VCC12_29") (pintype "passive"))
      (node (ref "U3") (pin "32") (pinfunction "VCC12_32") (pintype "passive"))
      (node (ref "U3") (pin "4") (pinfunction "VCC12_4") (pintype "passive"))
      (node (ref "U3") (pin "40") (pinfunction "VCC12_40") (pintype "passive"))
    )
    (net (code "94") (name "VCC1V2-B") (class "Default")
      (node (ref "C34") (pin "2") (pinfunction "2_2") (pintype "passive"))
      (node (ref "C35") (pin "2") (pinfunction "2_2") (pintype "passive"))
      (node (ref "C46") (pin "2") (pinfunction "2_2") (pintype "passive"))
      (node (ref "C47") (pin "2") (pinfunction "2_2") (pintype "passive"))
      (node (ref "C48") (pin "2") (pinfunction "2_2") (pintype "passive"))
      (node (ref "C49") (pin "2") (pinfunction "2_2") (pintype "passive"))
      (node (ref "C50") (pin "2") (pinfunction "2_2") (pintype "passive"))
      (node (ref "C51") (pin "2") (pinfunction "2_2") (pintype "passive"))
      (node (ref "C52") (pin "2") (pinfunction "2_2") (pintype "passive"))
      (node (ref "C53") (pin "2") (pinfunction "2_2") (pintype "passive"))
      (node (ref "L5") (pin "2") (pinfunction "2_2") (pintype "passive"))
      (node (ref "U4") (pin "10") (pinfunction "VCC12_10") (pintype "passive"))
      (node (ref "U4") (pin "18") (pinfunction "VCC12_18") (pintype "passive"))
      (node (ref "U4") (pin "21") (pinfunction "VCC12_21") (pintype "passive"))
      (node (ref "U4") (pin "24") (pinfunction "VCC12_24") (pintype "passive"))
      (node (ref "U4") (pin "29") (pinfunction "VCC12_29") (pintype "passive"))
      (node (ref "U4") (pin "32") (pinfunction "VCC12_32") (pintype "passive"))
      (node (ref "U4") (pin "4") (pinfunction "VCC12_4") (pintype "passive"))
      (node (ref "U4") (pin "40") (pinfunction "VCC12_40") (pintype "passive"))
    )
    (net (code "95") (name "VCC1V2-C") (class "Default")
      (node (ref "C75") (pin "2") (pinfunction "2_2") (pintype "passive"))
      (node (ref "C76") (pin "2") (pinfunction "2_2") (pintype "passive"))
      (node (ref "C78") (pin "2") (pinfunction "2_2") (pintype "passive"))
      (node (ref "C79") (pin "2") (pinfunction "2_2") (pintype "passive"))
      (node (ref "C80") (pin "2") (pinfunction "2_2") (pintype "passive"))
      (node (ref "C81") (pin "2") (pinfunction "2_2") (pintype "passive"))
      (node (ref "C82") (pin "2") (pinfunction "2_2") (pintype "passive"))
      (node (ref "C83") (pin "2") (pinfunction "2_2") (pintype "passive"))
      (node (ref "C84") (pin "2") (pinfunction "2_2") (pintype "passive"))
      (node (ref "C85") (pin "2") (pinfunction "2_2") (pintype "passive"))
      (node (ref "L6") (pin "2") (pinfunction "2_2") (pintype "passive"))
      (node (ref "U7") (pin "10") (pinfunction "VCC12_10") (pintype "passive"))
      (node (ref "U7") (pin "18") (pinfunction "VCC12_18") (pintype "passive"))
      (node (ref "U7") (pin "21") (pinfunction "VCC12_21") (pintype "passive"))
      (node (ref "U7") (pin "24") (pinfunction "VCC12_24") (pintype "passive"))
      (node (ref "U7") (pin "29") (pinfunction "VCC12_29") (pintype "passive"))
      (node (ref "U7") (pin "32") (pinfunction "VCC12_32") (pintype "passive"))
      (node (ref "U7") (pin "4") (pinfunction "VCC12_4") (pintype "passive"))
      (node (ref "U7") (pin "40") (pinfunction "VCC12_40") (pintype "passive"))
    )
    (net (code "96") (name "VCC3V3-A") (class "Default")
      (node (ref "C36") (pin "2") (pinfunction "2_2") (pintype "passive"))
      (node (ref "C56") (pin "2") (pinfunction "2_2") (pintype "passive"))
      (node (ref "C57") (pin "2") (pinfunction "2_2") (pintype "passive"))
      (node (ref "C58") (pin "2") (pinfunction "2_2") (pintype "passive"))
      (node (ref "C59") (pin "2") (pinfunction "2_2") (pintype "passive"))
      (node (ref "R26") (pin "1") (pinfunction "1_1") (pintype "passive"))
      (node (ref "R28") (pin "1") (pinfunction "1_1") (pintype "passive"))
      (node (ref "R32") (pin "1") (pinfunction "1_1") (pintype "passive"))
      (node (ref "U3") (pin "14") (pinfunction "VCC33_14") (pintype "passive"))
      (node (ref "U3") (pin "39") (pinfunction "VCC33_39") (pintype "passive"))
      (node (ref "U3") (pin "46") (pinfunction "MODE0_46") (pintype "passive"))
      (node (ref "U3") (pin "7") (pinfunction "VCC33_7") (pintype "passive"))
      (node (ref "U5") (pin "3") (pinfunction "WP#_3") (pintype "passive"))
      (node (ref "U5") (pin "7") (pinfunction "HOLD#_7") (pintype "passive"))
      (node (ref "U5") (pin "8") (pinfunction "VCC_8") (pintype "passive"))
    )
    (net (code "97") (name "VCC3V3-B") (class "Default")
      (node (ref "C37") (pin "2") (pinfunction "2_2") (pintype "passive"))
      (node (ref "C62") (pin "2") (pinfunction "2_2") (pintype "passive"))
      (node (ref "C63") (pin "2") (pinfunction "2_2") (pintype "passive"))
      (node (ref "C64") (pin "2") (pinfunction "2_2") (pintype "passive"))
      (node (ref "C65") (pin "2") (pinfunction "2_2") (pintype "passive"))
      (node (ref "R27") (pin "1") (pinfunction "1_1") (pintype "passive"))
      (node (ref "R29") (pin "1") (pinfunction "1_1") (pintype "passive"))
      (node (ref "R33") (pin "1") (pinfunction "1_1") (pintype "passive"))
      (node (ref "U4") (pin "14") (pinfunction "VCC33_14") (pintype "passive"))
      (node (ref "U4") (pin "39") (pinfunction "VCC33_39") (pintype "passive"))
      (node (ref "U4") (pin "46") (pinfunction "MODE0_46") (pintype "passive"))
      (node (ref "U4") (pin "7") (pinfunction "VCC33_7") (pintype "passive"))
      (node (ref "U6") (pin "3") (pinfunction "WP#_3") (pintype "passive"))
      (node (ref "U6") (pin "7") (pinfunction "HOLD#_7") (pintype "passive"))
      (node (ref "U6") (pin "8") (pinfunction "VCC_8") (pintype "passive"))
    )
    (net (code "98") (name "VCC3V3-C") (class "Default")
      (node (ref "C77") (pin "2") (pinfunction "2_2") (pintype "passive"))
      (node (ref "C88") (pin "2") (pinfunction "2_2") (pintype "passive"))
      (node (ref "C89") (pin "2") (pinfunction "2_2") (pintype "passive"))
      (node (ref "C90") (pin "2") (pinfunction "2_2") (pintype "passive"))
      (node (ref "C91") (pin "2") (pinfunction "2_2") (pintype "passive"))
      (node (ref "R34") (pin "1") (pinfunction "1_1") (pintype "passive"))
      (node (ref "R35") (pin "1") (pinfunction "1_1") (pintype "passive"))
      (node (ref "R37") (pin "1") (pinfunction "1_1") (pintype "passive"))
      (node (ref "U7") (pin "14") (pinfunction "VCC33_14") (pintype "passive"))
      (node (ref "U7") (pin "39") (pinfunction "VCC33_39") (pintype "passive"))
      (node (ref "U7") (pin "46") (pinfunction "MODE0_46") (pintype "passive"))
      (node (ref "U7") (pin "7") (pinfunction "VCC33_7") (pintype "passive"))
      (node (ref "U8") (pin "3") (pinfunction "WP#_3") (pintype "passive"))
      (node (ref "U8") (pin "7") (pinfunction "HOLD#_7") (pintype "passive"))
      (node (ref "U8") (pin "8") (pinfunction "VCC_8") (pintype "passive"))
    )
    (net (code "99") (name "unconnected-(U3-GPIO7-Pad41)") (class "Default")
      (node (ref "U3") (pin "41") (pinfunction "GPIO7_41") (pintype "passive+no_connect"))
    )
    (net (code "100") (name "unconnected-(U3-GPIO9-Pad48)") (class "Default")
      (node (ref "U3") (pin "48") (pinfunction "GPIO9_48") (pintype "passive+no_connect"))
    )
    (net (code "101") (name "unconnected-(U3-NC-Pad16)") (class "Default")
      (node (ref "U3") (pin "16") (pinfunction "NC_16") (pintype "passive+no_connect"))
    )
    (net (code "102") (name "unconnected-(U3-NC-Pad17)") (class "Default")
      (node (ref "U3") (pin "17") (pinfunction "NC_17") (pintype "passive+no_connect"))
    )
    (net (code "103") (name "unconnected-(U3-NC-Pad25)") (class "Default")
      (node (ref "U3") (pin "25") (pinfunction "NC_25") (pintype "passive+no_connect"))
    )
    (net (code "104") (name "unconnected-(U3-NC-Pad35)") (class "Default")
      (node (ref "U3") (pin "35") (pinfunction "NC_35") (pintype "passive+no_connect"))
    )
    (net (code "105") (name "unconnected-(U4-GPIO7-Pad41)") (class "Default")
      (node (ref "U4") (pin "41") (pinfunction "GPIO7_41") (pintype "passive+no_connect"))
    )
    (net (code "106") (name "unconnected-(U4-GPIO9-Pad48)") (class "Default")
      (node (ref "U4") (pin "48") (pinfunction "GPIO9_48") (pintype "passive+no_connect"))
    )
    (net (code "107") (name "unconnected-(U4-NC-Pad16)") (class "Default")
      (node (ref "U4") (pin "16") (pinfunction "NC_16") (pintype "passive+no_connect"))
    )
    (net (code "108") (name "unconnected-(U4-NC-Pad17)") (class "Default")
      (node (ref "U4") (pin "17") (pinfunction "NC_17") (pintype "passive+no_connect"))
    )
    (net (code "109") (name "unconnected-(U4-NC-Pad25)") (class "Default")
      (node (ref "U4") (pin "25") (pinfunction "NC_25") (pintype "passive+no_connect"))
    )
    (net (code "110") (name "unconnected-(U4-NC-Pad35)") (class "Default")
      (node (ref "U4") (pin "35") (pinfunction "NC_35") (pintype "passive+no_connect"))
    )
    (net (code "111") (name "unconnected-(U7-GPIO7-Pad41)") (class "Default")
      (node (ref "U7") (pin "41") (pinfunction "GPIO7_41") (pintype "passive+no_connect"))
    )
    (net (code "112") (name "unconnected-(U7-GPIO9-Pad48)") (class "Default")
      (node (ref "U7") (pin "48") (pinfunction "GPIO9_48") (pintype "passive+no_connect"))
    )
    (net (code "113") (name "unconnected-(U7-NC-Pad16)") (class "Default")
      (node (ref "U7") (pin "16") (pinfunction "NC_16") (pintype "passive+no_connect"))
    )
    (net (code "114") (name "unconnected-(U7-NC-Pad17)") (class "Default")
      (node (ref "U7") (pin "17") (pinfunction "NC_17") (pintype "passive+no_connect"))
    )
    (net (code "115") (name "unconnected-(U7-NC-Pad25)") (class "Default")
      (node (ref "U7") (pin "25") (pinfunction "NC_25") (pintype "passive+no_connect"))
    )
    (net (code "116") (name "unconnected-(U7-NC-Pad35)") (class "Default")
      (node (ref "U7") (pin "35") (pinfunction "NC_35") (pintype "passive+no_connect"))
    )
  )
)
